# Joystick_Controller.net
KiCad netlist of a schematic drawn in EAGLE
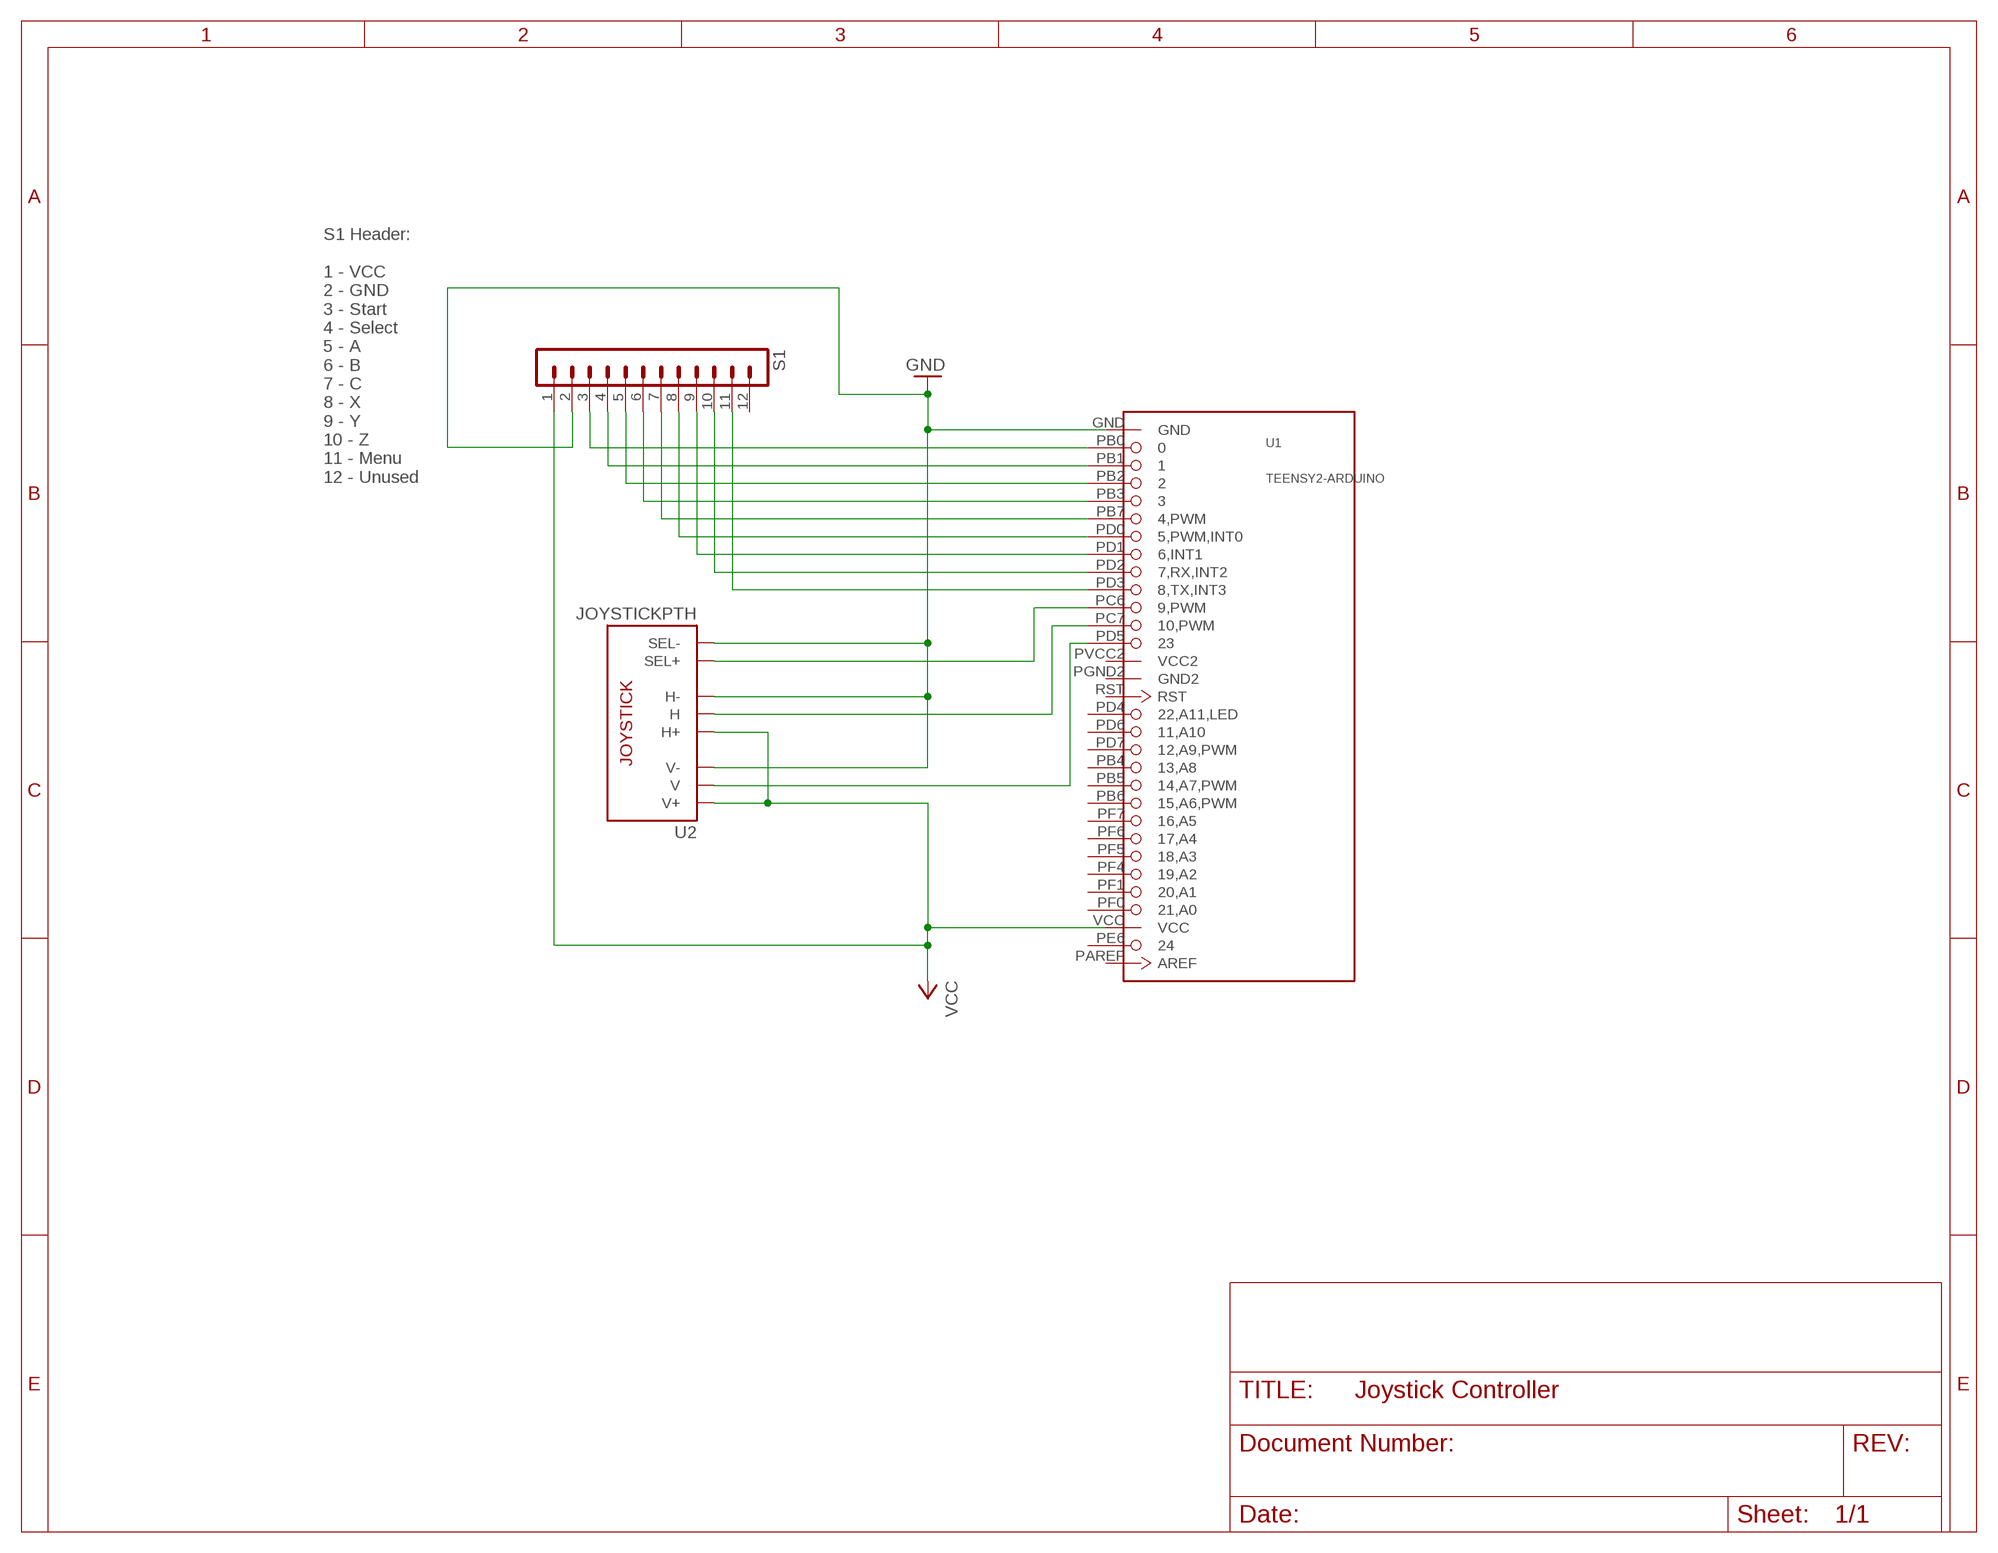
[diagram p0: schematic, sheet 1]

(export (version "E")
  (design (tool "Eeschema 10.0.6"))
  (components
    (comp (ref "S1")
      (value "MA12-1")
      (footprint "eagle-import:MA12-1")
      (libsource (lib "eagle-import") (part "MA12-1"))
    )
    (comp (ref "U1")
      (value "TEENSY2-ARDUINO")
      (footprint "eagle-import:TEENSY2")
      (libsource (lib "eagle-import") (part "TEENSY2-ARDUINO"))
    )
    (comp (ref "U2")
      (value "JOYSTICKPTH")
      (footprint "eagle-import:JOYSTICK")
      (libsource (lib "eagle-import") (part "JOYSTICKPTH"))
    )
  )
  (nets
    (net (code "1") (name "/GND2") (class "Default")
      (node (ref "U1") (pin "PGND2") (pinfunction "GND2_PGND2") (pintype "power_in"))
    )
    (net (code "2") (name "/VCC2") (class "Default")
      (node (ref "U1") (pin "PVCC2") (pinfunction "VCC2_PVCC2") (pintype "power_in"))
    )
    (net (code "3") (name "GND") (class "Default")
      (node (ref "S1") (pin "2") (pinfunction "2_2") (pintype "passive"))
      (node (ref "U1") (pin "GND") (pinfunction "GND_GND") (pintype "power_in"))
      (node (ref "U2") (pin "B2A") (pinfunction "SEL-_B2A") (pintype "bidirectional"))
      (node (ref "U2") (pin "H3") (pinfunction "H-_H3") (pintype "bidirectional"))
      (node (ref "U2") (pin "V3") (pinfunction "V-_V3") (pintype "bidirectional"))
    )
    (net (code "4") (name "Net-(U1-0)") (class "Default")
      (node (ref "S1") (pin "3") (pinfunction "3_3") (pintype "passive"))
      (node (ref "U1") (pin "PB0") (pinfunction "0_PB0") (pintype "bidirectional"))
    )
    (net (code "5") (name "Net-(U1-1)") (class "Default")
      (node (ref "S1") (pin "4") (pinfunction "4_4") (pintype "passive"))
      (node (ref "U1") (pin "PB1") (pinfunction "1_PB1") (pintype "bidirectional"))
    )
    (net (code "6") (name "Net-(U1-2)") (class "Default")
      (node (ref "S1") (pin "5") (pinfunction "5_5") (pintype "passive"))
      (node (ref "U1") (pin "PB2") (pinfunction "2_PB2") (pintype "bidirectional"))
    )
    (net (code "7") (name "Net-(U1-3)") (class "Default")
      (node (ref "S1") (pin "6") (pinfunction "6_6") (pintype "passive"))
      (node (ref "U1") (pin "PB3") (pinfunction "3_PB3") (pintype "bidirectional"))
    )
    (net (code "8") (name "Net-(U1-4,PWM)") (class "Default")
      (node (ref "S1") (pin "7") (pinfunction "7_7") (pintype "passive"))
      (node (ref "U1") (pin "PB7") (pinfunction "4,PWM_PB7") (pintype "bidirectional"))
    )
    (net (code "9") (name "Net-(U1-5,PWM,INT0)") (class "Default")
      (node (ref "S1") (pin "8") (pinfunction "8_8") (pintype "passive"))
      (node (ref "U1") (pin "PD0") (pinfunction "5,PWM,INT0_PD0") (pintype "bidirectional"))
    )
    (net (code "10") (name "Net-(U1-6,INT1)") (class "Default")
      (node (ref "S1") (pin "9") (pinfunction "9_9") (pintype "passive"))
      (node (ref "U1") (pin "PD1") (pinfunction "6,INT1_PD1") (pintype "bidirectional"))
    )
    (net (code "11") (name "Net-(U1-7,RX,INT2)") (class "Default")
      (node (ref "S1") (pin "10") (pinfunction "10_10") (pintype "passive"))
      (node (ref "U1") (pin "PD2") (pinfunction "7,RX,INT2_PD2") (pintype "bidirectional"))
    )
    (net (code "12") (name "Net-(U1-8,TX,INT3)") (class "Default")
      (node (ref "S1") (pin "11") (pinfunction "11_11") (pintype "passive"))
      (node (ref "U1") (pin "PD3") (pinfunction "8,TX,INT3_PD3") (pintype "bidirectional"))
    )
    (net (code "13") (name "Net-(U1-9,PWM)") (class "Default")
      (node (ref "U1") (pin "PC6") (pinfunction "9,PWM_PC6") (pintype "bidirectional"))
      (node (ref "U2") (pin "B1A") (pinfunction "SEL+_B1A") (pintype "bidirectional"))
    )
    (net (code "14") (name "Net-(U1-10,PWM)") (class "Default")
      (node (ref "U1") (pin "PC7") (pinfunction "10,PWM_PC7") (pintype "bidirectional"))
      (node (ref "U2") (pin "H2") (pinfunction "H_H2") (pintype "bidirectional"))
    )
    (net (code "15") (name "Net-(U1-23)") (class "Default")
      (node (ref "U1") (pin "PD5") (pinfunction "23_PD5") (pintype "bidirectional"))
      (node (ref "U2") (pin "V2") (pinfunction "V_V2") (pintype "bidirectional"))
    )
    (net (code "16") (name "VCC") (class "Default")
      (node (ref "S1") (pin "1") (pinfunction "1_1") (pintype "passive"))
      (node (ref "U1") (pin "VCC") (pinfunction "VCC_VCC") (pintype "power_in"))
      (node (ref "U2") (pin "H1") (pinfunction "H+_H1") (pintype "bidirectional"))
      (node (ref "U2") (pin "V1") (pinfunction "V+_V1") (pintype "bidirectional"))
    )
    (net (code "17") (name "unconnected-(S1-Pad12)") (class "Default")
      (node (ref "S1") (pin "12") (pinfunction "12_12") (pintype "passive"))
    )
    (net (code "18") (name "unconnected-(U1-11,A10-PadPD6)") (class "Default")
      (node (ref "U1") (pin "PD6") (pinfunction "11,A10_PD6") (pintype "bidirectional"))
    )
    (net (code "19") (name "unconnected-(U1-12,A9,PWM-PadPD7)") (class "Default")
      (node (ref "U1") (pin "PD7") (pinfunction "12,A9,PWM_PD7") (pintype "bidirectional"))
    )
    (net (code "20") (name "unconnected-(U1-13,A8-PadPB4)") (class "Default")
      (node (ref "U1") (pin "PB4") (pinfunction "13,A8_PB4") (pintype "bidirectional"))
    )
    (net (code "21") (name "unconnected-(U1-14,A7,PWM-PadPB5)") (class "Default")
      (node (ref "U1") (pin "PB5") (pinfunction "14,A7,PWM_PB5") (pintype "bidirectional"))
    )
    (net (code "22") (name "unconnected-(U1-15,A6,PWM-PadPB6)") (class "Default")
      (node (ref "U1") (pin "PB6") (pinfunction "15,A6,PWM_PB6") (pintype "bidirectional"))
    )
    (net (code "23") (name "unconnected-(U1-16,A5-PadPF7)") (class "Default")
      (node (ref "U1") (pin "PF7") (pinfunction "16,A5_PF7") (pintype "bidirectional"))
    )
    (net (code "24") (name "unconnected-(U1-17,A4-PadPF6)") (class "Default")
      (node (ref "U1") (pin "PF6") (pinfunction "17,A4_PF6") (pintype "bidirectional"))
    )
    (net (code "25") (name "unconnected-(U1-18,A3-PadPF5)") (class "Default")
      (node (ref "U1") (pin "PF5") (pinfunction "18,A3_PF5") (pintype "bidirectional"))
    )
    (net (code "26") (name "unconnected-(U1-19,A2-PadPF4)") (class "Default")
      (node (ref "U1") (pin "PF4") (pinfunction "19,A2_PF4") (pintype "bidirectional"))
    )
    (net (code "27") (name "unconnected-(U1-20,A1-PadPF1)") (class "Default")
      (node (ref "U1") (pin "PF1") (pinfunction "20,A1_PF1") (pintype "bidirectional"))
    )
    (net (code "28") (name "unconnected-(U1-21,A0-PadPF0)") (class "Default")
      (node (ref "U1") (pin "PF0") (pinfunction "21,A0_PF0") (pintype "bidirectional"))
    )
    (net (code "29") (name "unconnected-(U1-22,A11,LED-PadPD4)") (class "Default")
      (node (ref "U1") (pin "PD4") (pinfunction "22,A11,LED_PD4") (pintype "bidirectional"))
    )
    (net (code "30") (name "unconnected-(U1-24-PadPE6)") (class "Default")
      (node (ref "U1") (pin "PE6") (pinfunction "24_PE6") (pintype "bidirectional"))
    )
    (net (code "31") (name "unconnected-(U1-AREF-PadPAREF)") (class "Default")
      (node (ref "U1") (pin "PAREF") (pinfunction "AREF_PAREF") (pintype "input"))
    )
    (net (code "32") (name "unconnected-(U1-PadRST)") (class "Default")
      (node (ref "U1") (pin "RST") (pinfunction "RST_RST") (pintype "input"))
    )
  )
)
